# V2_0.net
KiCad netlist of a schematic drawn in Altium Designer
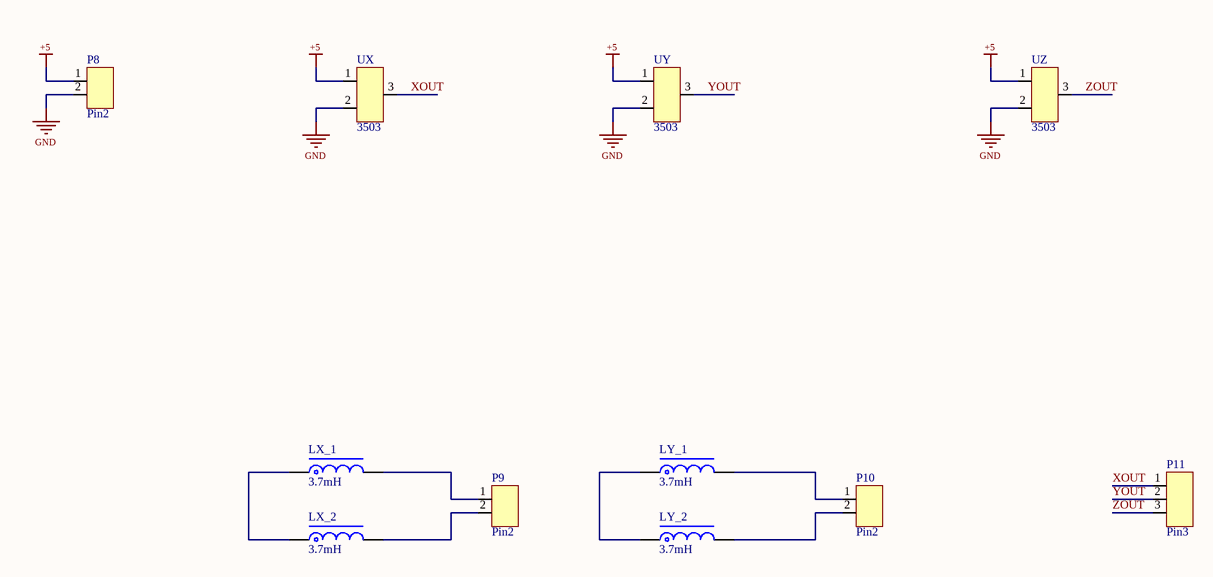
[diagram p0: 线圈主板V2.0.SchDoc]

(export (version "E")
  (design (tool "Eeschema 10.0.6"))
  (components
    (comp (ref "LX_1")
      (value "3.7mH")
      (footprint "线圈")
      (description "功率磁环电感")
      (fields (field (name "版权归属") "源创客"))
      (libsource (lib "3.1   - 电阻-电容-电感") (part "L-MR"))
    )
    (comp (ref "LX_2")
      (value "3.7mH")
      (footprint "线圈")
      (description "功率磁环电感")
      (fields (field (name "版权归属") "源创客"))
      (libsource (lib "3.1   - 电阻-电容-电感") (part "L-MR"))
    )
    (comp (ref "LY_1")
      (value "3.7mH")
      (footprint "线圈")
      (description "功率磁环电感")
      (fields (field (name "版权归属") "源创客"))
      (libsource (lib "3.1   - 电阻-电容-电感") (part "L-MR"))
    )
    (comp (ref "LY_2")
      (value "3.7mH")
      (footprint "线圈")
      (description "功率磁环电感")
      (fields (field (name "版权归属") "源创客"))
      (libsource (lib "3.1   - 电阻-电容-电感") (part "L-MR"))
    )
    (comp (ref "P8")
      (value "Pin2")
      (footprint "HDR2.54-LI-2P")
      (description "两脚2.54mm排针")
      (libsource (lib "Schlib1") (part "Pin2"))
    )
    (comp (ref "P9")
      (value "Pin2")
      (footprint "HDR2.54-LI-2P")
      (description "接L298N输出端口")
      (libsource (lib "Schlib1") (part "L298N"))
    )
    (comp (ref "P10")
      (value "Pin2")
      (footprint "HDR2.54-LI-2P")
      (description "接L298N输出端口")
      (libsource (lib "Schlib1") (part "L298N"))
    )
    (comp (ref "P11")
      (value "Pin3")
      (footprint "HDR2.54-LI-3P")
      (description "三脚2.54mm排针")
      (libsource (lib "Schlib1") (part "Pin3"))
    )
    (comp (ref "UX")
      (value "3503")
      (footprint "49E")
      (description "49E线性霍尔元件")
      (libsource (lib "Schlib1") (part "49E"))
    )
    (comp (ref "UY")
      (value "3503")
      (footprint "49E")
      (description "49E线性霍尔元件")
      (libsource (lib "Schlib1") (part "49E"))
    )
    (comp (ref "UZ")
      (value "3503")
      (footprint "49E")
      (description "49E线性霍尔元件")
      (libsource (lib "Schlib1") (part "49E"))
    )
  )
  (nets
    (net (code "1") (name "+5") (class "Default")
      (node (ref "P8") (pin "1") (pinfunction "1_1") (pintype "passive"))
      (node (ref "UX") (pin "1") (pinfunction "VCC_1") (pintype "passive"))
      (node (ref "UY") (pin "1") (pinfunction "VCC_1") (pintype "passive"))
      (node (ref "UZ") (pin "1") (pinfunction "VCC_1") (pintype "passive"))
    )
    (net (code "2") (name "/XOUT") (class "Default")
      (node (ref "P11") (pin "1") (pinfunction "1_1") (pintype "passive"))
      (node (ref "UX") (pin "3") (pinfunction "OUT_3") (pintype "passive"))
    )
    (net (code "3") (name "/YOUT") (class "Default")
      (node (ref "P11") (pin "2") (pinfunction "2_2") (pintype "passive"))
      (node (ref "UY") (pin "3") (pinfunction "OUT_3") (pintype "passive"))
    )
    (net (code "4") (name "/ZOUT") (class "Default")
      (node (ref "P11") (pin "3") (pinfunction "3_3") (pintype "passive"))
      (node (ref "UZ") (pin "3") (pinfunction "OUT_3") (pintype "passive"))
    )
    (net (code "5") (name "GND") (class "Default")
      (node (ref "P8") (pin "2") (pinfunction "2_2") (pintype "passive"))
      (node (ref "UX") (pin "2") (pinfunction "GND_2") (pintype "passive"))
      (node (ref "UY") (pin "2") (pinfunction "GND_2") (pintype "passive"))
      (node (ref "UZ") (pin "2") (pinfunction "GND_2") (pintype "passive"))
    )
    (net (code "6") (name "Net-(LX_1-Pad1)") (class "Default")
      (node (ref "LX_1") (pin "1") (pinfunction "1_1") (pintype "passive"))
      (node (ref "LX_2") (pin "1") (pinfunction "1_1") (pintype "passive"))
    )
    (net (code "7") (name "Net-(LX_1-Pad2)") (class "Default")
      (node (ref "LX_1") (pin "2") (pinfunction "2_2") (pintype "passive"))
      (node (ref "P9") (pin "1") (pinfunction "1_1") (pintype "passive"))
    )
    (net (code "8") (name "Net-(LX_2-Pad2)") (class "Default")
      (node (ref "LX_2") (pin "2") (pinfunction "2_2") (pintype "passive"))
      (node (ref "P9") (pin "2") (pinfunction "2_2") (pintype "passive"))
    )
    (net (code "9") (name "Net-(LY_1-Pad1)") (class "Default")
      (node (ref "LY_1") (pin "1") (pinfunction "1_1") (pintype "passive"))
      (node (ref "LY_2") (pin "1") (pinfunction "1_1") (pintype "passive"))
    )
    (net (code "10") (name "Net-(LY_1-Pad2)") (class "Default")
      (node (ref "LY_1") (pin "2") (pinfunction "2_2") (pintype "passive"))
      (node (ref "P10") (pin "1") (pinfunction "1_1") (pintype "passive"))
    )
    (net (code "11") (name "Net-(LY_2-Pad2)") (class "Default")
      (node (ref "LY_2") (pin "2") (pinfunction "2_2") (pintype "passive"))
      (node (ref "P10") (pin "2") (pinfunction "2_2") (pintype "passive"))
    )
  )
)
